# Sheet1.net
KiCad netlist of a schematic drawn in Altium Designer
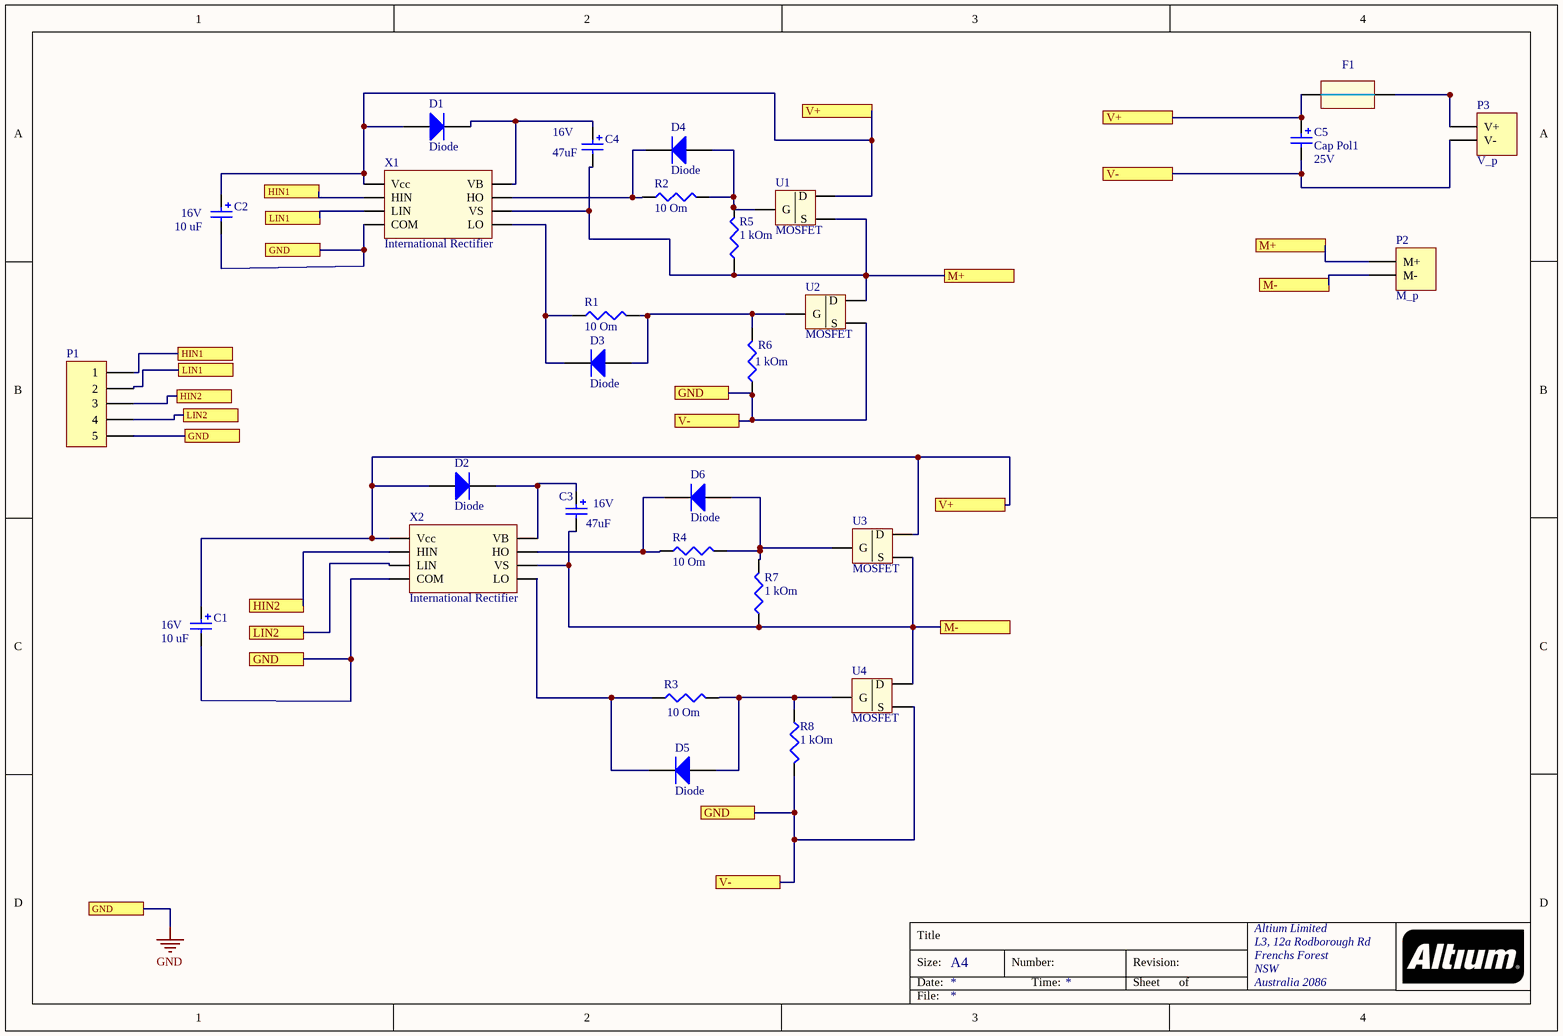
[diagram p0: Sheet1.SchDoc]

(export (version "E")
  (design (tool "Eeschema 10.0.6"))
  (components
    (comp (ref "C1")
      (value "16V")
      (footprint "smd cap")
      (description "Polarized Capacitor (Radial)")
      (fields (field (name "ALTIUM_VALUE") "10 uF") (field (name "PUBLISHER") "Altium Limited"))
      (libsource (lib "Schlib1") (part "Cap smd"))
    )
    (comp (ref "C2")
      (value "16V")
      (footprint "smd cap")
      (description "Polarized Capacitor (Radial)")
      (fields (field (name "ALTIUM_VALUE") "10 uF") (field (name "PUBLISHER") "Altium Limited"))
      (libsource (lib "Schlib1") (part "Cap smd"))
    )
    (comp (ref "C3")
      (value "16V")
      (footprint "smd cap")
      (description "Polarized Capacitor (Radial)")
      (fields (field (name "ALTIUM_VALUE") "47uF") (field (name "PUBLISHER") "Altium Limited"))
      (libsource (lib "Schlib1") (part "Cap smd"))
    )
    (comp (ref "C4")
      (value "16V")
      (footprint "smd cap")
      (description "Polarized Capacitor (Radial)")
      (fields (field (name "ALTIUM_VALUE") "47uF") (field (name "PUBLISHER") "Altium Limited"))
      (libsource (lib "Schlib1") (part "Cap smd"))
    )
    (comp (ref "C5")
      (value "Cap Pol1")
      (footprint "Cap El")
      (description "Polarized Capacitor (Radial)")
      (fields (field (name "ALTIUM_VALUE") "25V") (field (name "PUBLISHER") "Altium Limited"))
      (libsource (lib "Schlib1") (part "Cap smd"))
    )
    (comp (ref "D1")
      (value "Diode")
      (footprint "SOD123")
      (description "Default Diode")
      (fields (field (name "PUBLISHER") "Altium Limited"))
      (libsource (lib "Schlib1") (part "Diode"))
    )
    (comp (ref "D2")
      (value "Diode")
      (footprint "SOD123")
      (description "Default Diode")
      (fields (field (name "PUBLISHER") "Altium Limited"))
      (libsource (lib "Schlib1") (part "Diode"))
    )
    (comp (ref "D3")
      (value "Diode")
      (footprint "SOD123")
      (description "Default Diode")
      (fields (field (name "PUBLISHER") "Altium Limited"))
      (libsource (lib "Schlib1") (part "Diode"))
    )
    (comp (ref "D4")
      (value "Diode")
      (footprint "SOD123")
      (description "Default Diode")
      (fields (field (name "PUBLISHER") "Altium Limited"))
      (libsource (lib "Schlib1") (part "Diode"))
    )
    (comp (ref "D5")
      (value "Diode")
      (footprint "SOD123")
      (description "Default Diode")
      (fields (field (name "PUBLISHER") "Altium Limited"))
      (libsource (lib "Schlib1") (part "Diode"))
    )
    (comp (ref "D6")
      (value "Diode")
      (footprint "SOD123")
      (description "Default Diode")
      (fields (field (name "PUBLISHER") "Altium Limited"))
      (libsource (lib "Schlib1") (part "Diode"))
    )
    (comp (ref "F1") (value "Fuse") (footprint "FH-101") (libsource (lib "Schlib1") (part "FH-101")))
    (comp (ref "P1")
      (value "jst5")
      (footprint "JST5")
      (description "Header, 5-Pin")
      (fields (field (name "PUBLISHER") "Altium Limited"))
      (libsource (lib "Schlib1") (part "jst5"))
    )
    (comp (ref "P2") (value "M_p") (footprint "M_pin") (libsource (lib "Schlib1") (part "M_p")))
    (comp (ref "P3") (value "V_p") (footprint "V_pin") (libsource (lib "Schlib1") (part "V_p")))
    (comp (ref "R1")
      (value "10 Om")
      (footprint "14-1210")
      (description "Resistor")
      (fields (field (name "PUBLISHER") "Altium Limited"))
      (libsource (lib "Schlib1") (part "Res3"))
    )
    (comp (ref "R2")
      (value "10 Om")
      (footprint "14-1210")
      (description "Resistor")
      (fields (field (name "PUBLISHER") "Altium Limited"))
      (libsource (lib "Schlib1") (part "Res3"))
    )
    (comp (ref "R3")
      (value "10 Om")
      (footprint "14-1210")
      (description "Resistor")
      (fields (field (name "Comment") "Res3") (field (name "PUBLISHER") "Altium Limited"))
      (libsource (lib "Schlib1") (part "Res3"))
    )
    (comp (ref "R4")
      (value "10 Om")
      (footprint "14-1210")
      (description "Resistor")
      (fields (field (name "PUBLISHER") "Altium Limited"))
      (libsource (lib "Schlib1") (part "Res3"))
    )
    (comp (ref "R5")
      (value "1 kOm")
      (footprint "14-1210")
      (description "Resistor")
      (fields (field (name "PUBLISHER") "Altium Limited"))
      (libsource (lib "Schlib1") (part "Res3"))
    )
    (comp (ref "R6")
      (value "1 kOm")
      (footprint "14-1210")
      (description "Resistor")
      (fields (field (name "Comment") "Res3") (field (name "PUBLISHER") "Altium Limited"))
      (libsource (lib "Schlib1") (part "Res3"))
    )
    (comp (ref "R7")
      (value "1 kOm")
      (footprint "14-1210")
      (description "Resistor")
      (fields (field (name "PUBLISHER") "Altium Limited"))
      (libsource (lib "Schlib1") (part "Res3"))
    )
    (comp (ref "R8")
      (value "1 kOm")
      (footprint "14-1210")
      (description "Resistor")
      (fields (field (name "PUBLISHER") "Altium Limited"))
      (libsource (lib "Schlib1") (part "Res3"))
    )
    (comp (ref "U1")
      (value "MOSFET")
      (footprint "SMD220_10CTQ150")
      (libsource (lib "Schlib1") (part "IRFZ14PBF"))
    )
    (comp (ref "U2")
      (value "MOSFET")
      (footprint "SMD220_10CTQ150")
      (libsource (lib "Schlib1") (part "IRFZ14PBF"))
    )
    (comp (ref "U3")
      (value "MOSFET")
      (footprint "SMD220_10CTQ150")
      (libsource (lib "Schlib1") (part "IRFZ14PBF"))
    )
    (comp (ref "U4")
      (value "MOSFET")
      (footprint "SMD220_10CTQ150")
      (libsource (lib "Schlib1") (part "IRFZ14PBF"))
    )
    (comp (ref "X1")
      (value "International Rectifier")
      (footprint "SOIC8")
      (libsource (lib "Schlib1") (part "IR2101SPBF"))
    )
    (comp (ref "X2")
      (value "International Rectifier")
      (footprint "SOIC8")
      (libsource (lib "Schlib1") (part "IR2101SPBF"))
    )
  )
  (nets
    (net (code "1") (name "/HIN1") (class "Default")
      (node (ref "P1") (pin "1") (pinfunction "1_1") (pintype "passive"))
      (node (ref "X1") (pin "2") (pinfunction "HIN_2") (pintype "passive"))
    )
    (net (code "2") (name "/HIN2") (class "Default")
      (node (ref "P1") (pin "3") (pinfunction "3_3") (pintype "passive"))
      (node (ref "X2") (pin "2") (pinfunction "HIN_2") (pintype "passive"))
    )
    (net (code "3") (name "/LIN1") (class "Default")
      (node (ref "P1") (pin "2") (pinfunction "2_2") (pintype "passive"))
      (node (ref "X1") (pin "3") (pinfunction "LIN_3") (pintype "passive"))
    )
    (net (code "4") (name "/LIN2") (class "Default")
      (node (ref "P1") (pin "4") (pinfunction "4_4") (pintype "passive"))
      (node (ref "X2") (pin "3") (pinfunction "LIN_3") (pintype "passive"))
    )
    (net (code "5") (name "/M+") (class "Default")
      (node (ref "C4") (pin "2") (pinfunction "2_2") (pintype "passive"))
      (node (ref "P2") (pin "1") (pinfunction "M+_1") (pintype "passive"))
      (node (ref "R5") (pin "1") (pinfunction "1_1") (pintype "passive"))
      (node (ref "U1") (pin "3") (pinfunction "S_3") (pintype "passive"))
      (node (ref "U2") (pin "2") (pinfunction "D_2") (pintype "passive"))
      (node (ref "X1") (pin "6") (pinfunction "VS_6") (pintype "passive"))
    )
    (net (code "6") (name "/M-") (class "Default")
      (node (ref "C3") (pin "2") (pinfunction "2_2") (pintype "passive"))
      (node (ref "P2") (pin "2") (pinfunction "M-_2") (pintype "passive"))
      (node (ref "R7") (pin "1") (pinfunction "1_1") (pintype "passive"))
      (node (ref "U3") (pin "3") (pinfunction "S_3") (pintype "passive"))
      (node (ref "U4") (pin "2") (pinfunction "D_2") (pintype "passive"))
      (node (ref "X2") (pin "6") (pinfunction "VS_6") (pintype "passive"))
    )
    (net (code "7") (name "/V+") (class "Default")
      (node (ref "C1") (pin "1") (pinfunction "1_1") (pintype "passive"))
      (node (ref "C2") (pin "1") (pinfunction "1_1") (pintype "passive"))
      (node (ref "C5") (pin "1") (pinfunction "1_1") (pintype "passive"))
      (node (ref "D1") (pin "1") (pinfunction "A_1") (pintype "passive"))
      (node (ref "D2") (pin "1") (pinfunction "A_1") (pintype "passive"))
      (node (ref "F1") (pin "1") (pinfunction "1_1") (pintype "passive"))
      (node (ref "U1") (pin "2") (pinfunction "D_2") (pintype "passive"))
      (node (ref "U3") (pin "2") (pinfunction "D_2") (pintype "passive"))
      (node (ref "X1") (pin "1") (pinfunction "Vcc_1") (pintype "passive"))
      (node (ref "X2") (pin "1") (pinfunction "Vcc_1") (pintype "passive"))
    )
    (net (code "8") (name "GND") (class "Default")
      (node (ref "C1") (pin "2") (pinfunction "2_2") (pintype "passive"))
      (node (ref "C2") (pin "2") (pinfunction "2_2") (pintype "passive"))
      (node (ref "C5") (pin "2") (pinfunction "2_2") (pintype "passive"))
      (node (ref "P1") (pin "5") (pinfunction "5_5") (pintype "passive"))
      (node (ref "P3") (pin "2") (pinfunction "V-_2") (pintype "passive"))
      (node (ref "R6") (pin "1") (pinfunction "1_1") (pintype "passive"))
      (node (ref "R8") (pin "2") (pinfunction "2_2") (pintype "passive"))
      (node (ref "U2") (pin "3") (pinfunction "S_3") (pintype "passive"))
      (node (ref "U4") (pin "3") (pinfunction "S_3") (pintype "passive"))
      (node (ref "X1") (pin "4") (pinfunction "COM_4") (pintype "passive"))
      (node (ref "X2") (pin "4") (pinfunction "COM_4") (pintype "passive"))
    )
    (net (code "9") (name "Net-(D1-K)") (class "Default")
      (node (ref "C4") (pin "1") (pinfunction "1_1") (pintype "passive"))
      (node (ref "D1") (pin "2") (pinfunction "K_2") (pintype "passive"))
      (node (ref "X1") (pin "8") (pinfunction "VB_8") (pintype "passive"))
    )
    (net (code "10") (name "Net-(D2-K)") (class "Default")
      (node (ref "C3") (pin "1") (pinfunction "1_1") (pintype "passive"))
      (node (ref "D2") (pin "2") (pinfunction "K_2") (pintype "passive"))
      (node (ref "X2") (pin "8") (pinfunction "VB_8") (pintype "passive"))
    )
    (net (code "11") (name "Net-(D3-A)") (class "Default")
      (node (ref "D3") (pin "1") (pinfunction "A_1") (pintype "passive"))
      (node (ref "R1") (pin "2") (pinfunction "2_2") (pintype "passive"))
      (node (ref "R6") (pin "2") (pinfunction "2_2") (pintype "passive"))
      (node (ref "U2") (pin "1") (pinfunction "G_1") (pintype "passive"))
    )
    (net (code "12") (name "Net-(D3-K)") (class "Default")
      (node (ref "D3") (pin "2") (pinfunction "K_2") (pintype "passive"))
      (node (ref "R1") (pin "1") (pinfunction "1_1") (pintype "passive"))
      (node (ref "X1") (pin "5") (pinfunction "LO_5") (pintype "passive"))
    )
    (net (code "13") (name "Net-(D4-A)") (class "Default")
      (node (ref "D4") (pin "1") (pinfunction "A_1") (pintype "passive"))
      (node (ref "R2") (pin "2") (pinfunction "2_2") (pintype "passive"))
      (node (ref "R5") (pin "2") (pinfunction "2_2") (pintype "passive"))
      (node (ref "U1") (pin "1") (pinfunction "G_1") (pintype "passive"))
    )
    (net (code "14") (name "Net-(D4-K)") (class "Default")
      (node (ref "D4") (pin "2") (pinfunction "K_2") (pintype "passive"))
      (node (ref "R2") (pin "1") (pinfunction "1_1") (pintype "passive"))
      (node (ref "X1") (pin "7") (pinfunction "HO_7") (pintype "passive"))
    )
    (net (code "15") (name "Net-(D5-A)") (class "Default")
      (node (ref "D5") (pin "1") (pinfunction "A_1") (pintype "passive"))
      (node (ref "R3") (pin "2") (pinfunction "2_2") (pintype "passive"))
      (node (ref "R8") (pin "1") (pinfunction "1_1") (pintype "passive"))
      (node (ref "U4") (pin "1") (pinfunction "G_1") (pintype "passive"))
    )
    (net (code "16") (name "Net-(D5-K)") (class "Default")
      (node (ref "D5") (pin "2") (pinfunction "K_2") (pintype "passive"))
      (node (ref "R3") (pin "1") (pinfunction "1_1") (pintype "passive"))
      (node (ref "X2") (pin "5") (pinfunction "LO_5") (pintype "passive"))
    )
    (net (code "17") (name "Net-(D6-A)") (class "Default")
      (node (ref "D6") (pin "1") (pinfunction "A_1") (pintype "passive"))
      (node (ref "R4") (pin "2") (pinfunction "2_2") (pintype "passive"))
      (node (ref "R7") (pin "2") (pinfunction "2_2") (pintype "passive"))
      (node (ref "U3") (pin "1") (pinfunction "G_1") (pintype "passive"))
    )
    (net (code "18") (name "Net-(D6-K)") (class "Default")
      (node (ref "D6") (pin "2") (pinfunction "K_2") (pintype "passive"))
      (node (ref "R4") (pin "1") (pinfunction "1_1") (pintype "passive"))
      (node (ref "X2") (pin "7") (pinfunction "HO_7") (pintype "passive"))
    )
    (net (code "19") (name "Net-(P3-V+)") (class "Default")
      (node (ref "F1") (pin "2") (pinfunction "2_2") (pintype "passive"))
      (node (ref "P3") (pin "1") (pinfunction "V+_1") (pintype "passive"))
    )
  )
)
